# Top.net
KiCad netlist of a schematic drawn in Altium Designer
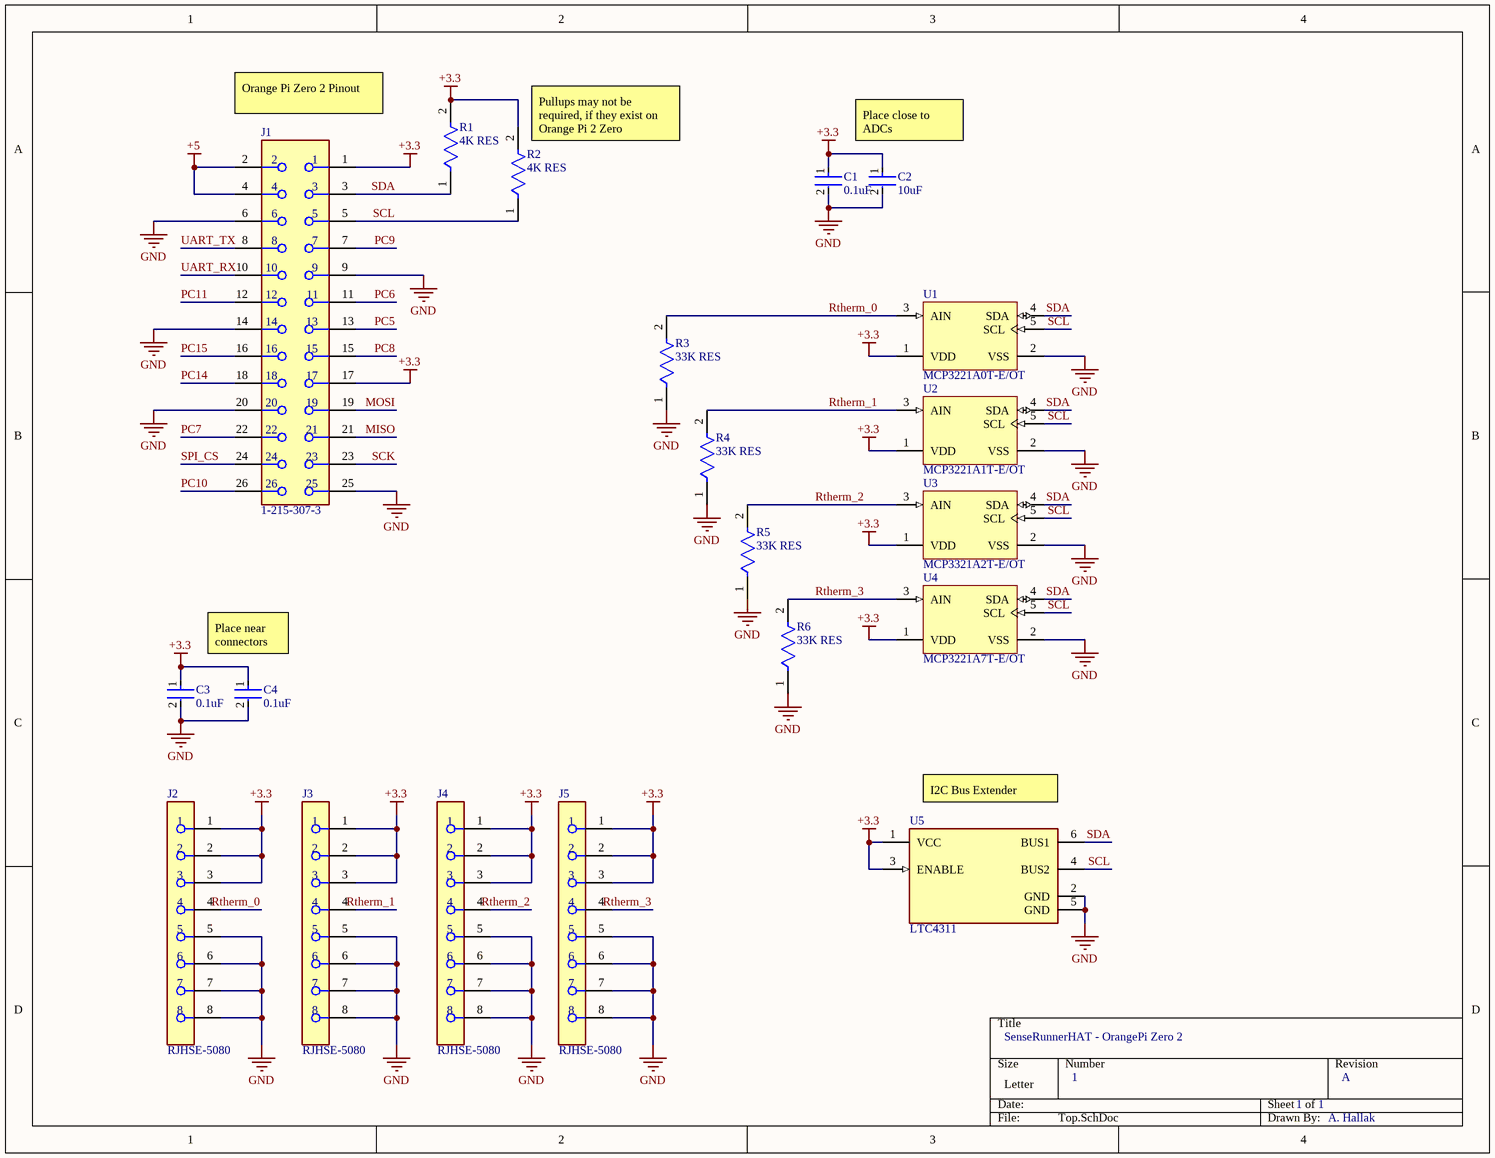
[diagram p0: Top.SchDoc]

(export (version "E")
  (design (tool "Eeschema 10.0.6"))
  (components
    (comp (ref "C1")
      (value "0.1uF")
      (footprint "FP-DE6_D7_T7_F7_5_d0_6-0-MFG")
      (description "CAP CER 0.1uF")
      (fields (field (name "PART NUMBER") "ANY 0.1uF CAP") (field (name "TOLERANCE") "20%"))
      (libsource (lib "Altium Content Vault") (part "7bc8f122f62ff4f5a687363419e79e3"))
    )
    (comp (ref "C2")
      (value "10uF")
      (footprint "FP-DE6_D7_T7_F7_5_d0_6-0-MFG")
      (description "CAP CER 10uF")
      (fields (field (name "PART NUMBER") "ANY 10uF CAP") (field (name "TOLERANCE") "20%"))
      (libsource (lib "Altium Content Vault") (part "7bc8f122f62ff4f5a687363419e79e3"))
    )
    (comp (ref "C3")
      (value "0.1uF")
      (footprint "FP-DE6_D7_T7_F7_5_d0_6-0-MFG")
      (description "CAP CER 0.1uF")
      (fields (field (name "PART NUMBER") "ANY 0.1uF CAP") (field (name "TOLERANCE") "20%"))
      (libsource (lib "Altium Content Vault") (part "7bc8f122f62ff4f5a687363419e79e3"))
    )
    (comp (ref "C4")
      (value "0.1uF")
      (footprint "FP-DE6_D7_T7_F7_5_d0_6-0-MFG")
      (description "CAP CER 0.1uF")
      (fields (field (name "PART NUMBER") "ANY 0.1uF CAP") (field (name "TOLERANCE") "20%"))
      (libsource (lib "Altium Content Vault") (part "7bc8f122f62ff4f5a687363419e79e3"))
    )
    (comp (ref "J1")
      (value "1-215-307-3")
      (footprint "Footprints:26PIN")
      (description "CONN HDR 26POS")
      (libsource (lib "Symbols") (part "CMP-25680-000025-1"))
    )
    (comp (ref "J2")
      (value "RJHSE-5080")
      (footprint "FP-RJHSE-5080-MFG")
      (description "CONN MOD JACK 8P8C R/A UNSHLD")
      (fields
        (field (name "OCTOPART") "https://octopart.com/rjhse-5080-amphenol-45060")
        (field (name "MANUFACTURER") "Amphenol")
      )
      (libsource (lib "Altium Content Vault") (part "b0a0b555dd3abf3683e7c330df25cc4"))
    )
    (comp (ref "J3")
      (value "RJHSE-5080")
      (footprint "FP-RJHSE-5080-MFG")
      (description "CONN MOD JACK 8P8C R/A UNSHLD")
      (fields
        (field (name "OCTOPART") "https://octopart.com/rjhse-5080-amphenol-45060")
        (field (name "MANUFACTURER") "Amphenol")
      )
      (libsource (lib "Altium Content Vault") (part "b0a0b555dd3abf3683e7c330df25cc4"))
    )
    (comp (ref "J4")
      (value "RJHSE-5080")
      (footprint "FP-RJHSE-5080-MFG")
      (description "CONN MOD JACK 8P8C R/A UNSHLD")
      (fields
        (field (name "OCTOPART") "https://octopart.com/rjhse-5080-amphenol-45060")
        (field (name "MANUFACTURER") "Amphenol")
      )
      (libsource (lib "Altium Content Vault") (part "b0a0b555dd3abf3683e7c330df25cc4"))
    )
    (comp (ref "J5")
      (value "RJHSE-5080")
      (footprint "FP-RJHSE-5080-MFG")
      (description "CONN MOD JACK 8P8C R/A UNSHLD")
      (fields
        (field (name "OCTOPART") "https://octopart.com/rjhse-5080-amphenol-45060")
        (field (name "MANUFACTURER") "Amphenol")
      )
      (libsource (lib "Altium Content Vault") (part "b0a0b555dd3abf3683e7c330df25cc4"))
    )
    (comp (ref "R1")
      (value "4K RES")
      (footprint "FP-H8-MFG")
      (description "RES 4K")
      (fields (field (name "PART NUMBER") "ANY 4K RESISTOR"))
      (libsource (lib "Altium Content Vault") (part "1029c3af85768c4190bb7ad29bc67b5"))
    )
    (comp (ref "R2")
      (value "4K RES")
      (footprint "FP-H8-MFG")
      (description "RES 4K")
      (fields (field (name "PART NUMBER") "ANY 4K RESISTOR"))
      (libsource (lib "Altium Content Vault") (part "1029c3af85768c4190bb7ad29bc67b5"))
    )
    (comp (ref "R3")
      (value "33K RES")
      (footprint "FP-H8-MFG")
      (description "RES 33K")
      (fields (field (name "PART NUMBER") "ANY RES - RSET"))
      (libsource (lib "Altium Content Vault") (part "1029c3af85768c4190bb7ad29bc67b5"))
    )
    (comp (ref "R4")
      (value "33K RES")
      (footprint "FP-H8-MFG")
      (description "RES 33K")
      (fields (field (name "PART NUMBER") "ANY RES - RSET"))
      (libsource (lib "Altium Content Vault") (part "1029c3af85768c4190bb7ad29bc67b5"))
    )
    (comp (ref "R5")
      (value "33K RES")
      (footprint "FP-H8-MFG")
      (description "RES 33K")
      (fields (field (name "PART NUMBER") "ANY RES - RSET"))
      (libsource (lib "Altium Content Vault") (part "1029c3af85768c4190bb7ad29bc67b5"))
    )
    (comp (ref "R6")
      (value "33K RES")
      (footprint "FP-H8-MFG")
      (description "RES 33K")
      (fields (field (name "PART NUMBER") "ANY RES - RSET"))
      (libsource (lib "Altium Content Vault") (part "1029c3af85768c4190bb7ad29bc67b5"))
    )
    (comp (ref "U1")
      (value "MCP3221A0T-E/OT")
      (footprint "SOT-23-OT5_N")
      (libsource (lib "Altium Content Vault") (part "CON-ADC-MCP3021-5"))
    )
    (comp (ref "U2")
      (value "MCP3221A1T-E/OT")
      (footprint "SOT-23-OT5_N")
      (libsource (lib "Altium Content Vault") (part "CON-ADC-MCP3021-5"))
    )
    (comp (ref "U3")
      (value "MCP3321A2T-E/OT")
      (footprint "SOT-23-OT5_N")
      (libsource (lib "Altium Content Vault") (part "CON-ADC-MCP3021-5"))
    )
    (comp (ref "U4")
      (value "MCP3221A7T-E/OT")
      (footprint "SOT-23-OT5_N")
      (fields (field (name "PART NUMBER") "MCP3321A7T-E/OT"))
      (libsource (lib "Altium Content Vault") (part "CON-ADC-MCP3021-5"))
    )
    (comp (ref "U5")
      (value "LTC4311")
      (footprint "FP-SC6-6-05-08-1638-IPC_C")
      (description "IC ACCELERATOR I2C 1CH SC70-6")
      (libsource (lib "Altium Content Vault") (part "8960268e019b227b8cf571965444921"))
    )
  )
  (nets
    (net (code "1") (name "+3.3") (class "Default")
      (node (ref "C1") (pin "1") (pinfunction "1_1") (pintype "passive"))
      (node (ref "C2") (pin "1") (pinfunction "1_1") (pintype "passive"))
      (node (ref "C3") (pin "1") (pinfunction "1_1") (pintype "passive"))
      (node (ref "C4") (pin "1") (pinfunction "1_1") (pintype "passive"))
      (node (ref "J1") (pin "1") (pinfunction "1_1") (pintype "passive"))
      (node (ref "J1") (pin "17") (pinfunction "17_17") (pintype "passive"))
      (node (ref "J2") (pin "1") (pinfunction "1_1") (pintype "passive"))
      (node (ref "J2") (pin "2") (pinfunction "2_2") (pintype "passive"))
      (node (ref "J2") (pin "3") (pinfunction "3_3") (pintype "passive"))
      (node (ref "J3") (pin "1") (pinfunction "1_1") (pintype "passive"))
      (node (ref "J3") (pin "2") (pinfunction "2_2") (pintype "passive"))
      (node (ref "J3") (pin "3") (pinfunction "3_3") (pintype "passive"))
      (node (ref "J4") (pin "1") (pinfunction "1_1") (pintype "passive"))
      (node (ref "J4") (pin "2") (pinfunction "2_2") (pintype "passive"))
      (node (ref "J4") (pin "3") (pinfunction "3_3") (pintype "passive"))
      (node (ref "J5") (pin "1") (pinfunction "1_1") (pintype "passive"))
      (node (ref "J5") (pin "2") (pinfunction "2_2") (pintype "passive"))
      (node (ref "J5") (pin "3") (pinfunction "3_3") (pintype "passive"))
      (node (ref "R1") (pin "2") (pinfunction "2_2") (pintype "passive"))
      (node (ref "R2") (pin "2") (pinfunction "2_2") (pintype "passive"))
      (node (ref "U1") (pin "1") (pinfunction "VDD_1") (pintype "power_in"))
      (node (ref "U2") (pin "1") (pinfunction "VDD_1") (pintype "power_in"))
      (node (ref "U3") (pin "1") (pinfunction "VDD_1") (pintype "power_in"))
      (node (ref "U4") (pin "1") (pinfunction "VDD_1") (pintype "power_in"))
      (node (ref "U5") (pin "1") (pinfunction "VCC_1") (pintype "power_in"))
      (node (ref "U5") (pin "3") (pinfunction "ENABLE_3") (pintype "input"))
    )
    (net (code "2") (name "+5") (class "Default")
      (node (ref "J1") (pin "2") (pinfunction "2_2") (pintype "passive"))
      (node (ref "J1") (pin "4") (pinfunction "4_4") (pintype "passive"))
    )
    (net (code "3") (name "/MISO") (class "Default")
      (node (ref "J1") (pin "21") (pinfunction "21_21") (pintype "passive"))
    )
    (net (code "4") (name "/MOSI") (class "Default")
      (node (ref "J1") (pin "19") (pinfunction "19_19") (pintype "passive"))
    )
    (net (code "5") (name "/PC5") (class "Default")
      (node (ref "J1") (pin "13") (pinfunction "13_13") (pintype "passive"))
    )
    (net (code "6") (name "/PC6") (class "Default")
      (node (ref "J1") (pin "11") (pinfunction "11_11") (pintype "passive"))
    )
    (net (code "7") (name "/PC7") (class "Default")
      (node (ref "J1") (pin "22") (pinfunction "22_22") (pintype "passive"))
    )
    (net (code "8") (name "/PC8") (class "Default")
      (node (ref "J1") (pin "15") (pinfunction "15_15") (pintype "passive"))
    )
    (net (code "9") (name "/PC9") (class "Default")
      (node (ref "J1") (pin "7") (pinfunction "7_7") (pintype "passive"))
    )
    (net (code "10") (name "/PC10") (class "Default")
      (node (ref "J1") (pin "26") (pinfunction "26_26") (pintype "passive"))
    )
    (net (code "11") (name "/PC11") (class "Default")
      (node (ref "J1") (pin "12") (pinfunction "12_12") (pintype "passive"))
    )
    (net (code "12") (name "/PC14") (class "Default")
      (node (ref "J1") (pin "18") (pinfunction "18_18") (pintype "passive"))
    )
    (net (code "13") (name "/PC15") (class "Default")
      (node (ref "J1") (pin "16") (pinfunction "16_16") (pintype "passive"))
    )
    (net (code "14") (name "/Rtherm_0") (class "Default")
      (node (ref "J2") (pin "4") (pinfunction "4_4") (pintype "passive"))
      (node (ref "R3") (pin "2") (pinfunction "2_2") (pintype "passive"))
      (node (ref "U1") (pin "3") (pinfunction "AIN_3") (pintype "input"))
    )
    (net (code "15") (name "/Rtherm_1") (class "Default")
      (node (ref "J3") (pin "4") (pinfunction "4_4") (pintype "passive"))
      (node (ref "R4") (pin "2") (pinfunction "2_2") (pintype "passive"))
      (node (ref "U2") (pin "3") (pinfunction "AIN_3") (pintype "input"))
    )
    (net (code "16") (name "/Rtherm_2") (class "Default")
      (node (ref "J4") (pin "4") (pinfunction "4_4") (pintype "passive"))
      (node (ref "R5") (pin "2") (pinfunction "2_2") (pintype "passive"))
      (node (ref "U3") (pin "3") (pinfunction "AIN_3") (pintype "input"))
    )
    (net (code "17") (name "/Rtherm_3") (class "Default")
      (node (ref "J5") (pin "4") (pinfunction "4_4") (pintype "passive"))
      (node (ref "R6") (pin "2") (pinfunction "2_2") (pintype "passive"))
      (node (ref "U4") (pin "3") (pinfunction "AIN_3") (pintype "input"))
    )
    (net (code "18") (name "/SCK") (class "Default")
      (node (ref "J1") (pin "23") (pinfunction "23_23") (pintype "passive"))
    )
    (net (code "19") (name "/SCL") (class "Default")
      (node (ref "J1") (pin "5") (pinfunction "5_5") (pintype "passive"))
      (node (ref "R2") (pin "1") (pinfunction "1_1") (pintype "passive"))
      (node (ref "U1") (pin "5") (pinfunction "SCL_5") (pintype "input"))
      (node (ref "U2") (pin "5") (pinfunction "SCL_5") (pintype "input"))
      (node (ref "U3") (pin "5") (pinfunction "SCL_5") (pintype "input"))
      (node (ref "U4") (pin "5") (pinfunction "SCL_5") (pintype "input"))
      (node (ref "U5") (pin "4") (pinfunction "BUS2_4") (pintype "passive"))
    )
    (net (code "20") (name "/SDA") (class "Default")
      (node (ref "J1") (pin "3") (pinfunction "3_3") (pintype "passive"))
      (node (ref "R1") (pin "1") (pinfunction "1_1") (pintype "passive"))
      (node (ref "U1") (pin "4") (pinfunction "SDA_4") (pintype "bidirectional"))
      (node (ref "U2") (pin "4") (pinfunction "SDA_4") (pintype "bidirectional"))
      (node (ref "U3") (pin "4") (pinfunction "SDA_4") (pintype "bidirectional"))
      (node (ref "U4") (pin "4") (pinfunction "SDA_4") (pintype "bidirectional"))
      (node (ref "U5") (pin "6") (pinfunction "BUS1_6") (pintype "passive"))
    )
    (net (code "21") (name "/SPI_CS") (class "Default")
      (node (ref "J1") (pin "24") (pinfunction "24_24") (pintype "passive"))
    )
    (net (code "22") (name "/UART_RX") (class "Default")
      (node (ref "J1") (pin "10") (pinfunction "10_10") (pintype "passive"))
    )
    (net (code "23") (name "/UART_TX") (class "Default")
      (node (ref "J1") (pin "8") (pinfunction "8_8") (pintype "passive"))
    )
    (net (code "24") (name "GND") (class "Default")
      (node (ref "C1") (pin "2") (pinfunction "2_2") (pintype "passive"))
      (node (ref "C2") (pin "2") (pinfunction "2_2") (pintype "passive"))
      (node (ref "C3") (pin "2") (pinfunction "2_2") (pintype "passive"))
      (node (ref "C4") (pin "2") (pinfunction "2_2") (pintype "passive"))
      (node (ref "J1") (pin "14") (pinfunction "14_14") (pintype "passive"))
      (node (ref "J1") (pin "20") (pinfunction "20_20") (pintype "passive"))
      (node (ref "J1") (pin "25") (pinfunction "25_25") (pintype "passive"))
      (node (ref "J1") (pin "6") (pinfunction "6_6") (pintype "passive"))
      (node (ref "J1") (pin "9") (pinfunction "9_9") (pintype "passive"))
      (node (ref "J2") (pin "5") (pinfunction "5_5") (pintype "passive"))
      (node (ref "J2") (pin "6") (pinfunction "6_6") (pintype "passive"))
      (node (ref "J2") (pin "7") (pinfunction "7_7") (pintype "passive"))
      (node (ref "J2") (pin "8") (pinfunction "8_8") (pintype "passive"))
      (node (ref "J3") (pin "5") (pinfunction "5_5") (pintype "passive"))
      (node (ref "J3") (pin "6") (pinfunction "6_6") (pintype "passive"))
      (node (ref "J3") (pin "7") (pinfunction "7_7") (pintype "passive"))
      (node (ref "J3") (pin "8") (pinfunction "8_8") (pintype "passive"))
      (node (ref "J4") (pin "5") (pinfunction "5_5") (pintype "passive"))
      (node (ref "J4") (pin "6") (pinfunction "6_6") (pintype "passive"))
      (node (ref "J4") (pin "7") (pinfunction "7_7") (pintype "passive"))
      (node (ref "J4") (pin "8") (pinfunction "8_8") (pintype "passive"))
      (node (ref "J5") (pin "5") (pinfunction "5_5") (pintype "passive"))
      (node (ref "J5") (pin "6") (pinfunction "6_6") (pintype "passive"))
      (node (ref "J5") (pin "7") (pinfunction "7_7") (pintype "passive"))
      (node (ref "J5") (pin "8") (pinfunction "8_8") (pintype "passive"))
      (node (ref "R3") (pin "1") (pinfunction "1_1") (pintype "passive"))
      (node (ref "R4") (pin "1") (pinfunction "1_1") (pintype "passive"))
      (node (ref "R5") (pin "1") (pinfunction "1_1") (pintype "passive"))
      (node (ref "R6") (pin "1") (pinfunction "1_1") (pintype "passive"))
      (node (ref "U1") (pin "2") (pinfunction "VSS_2") (pintype "power_in"))
      (node (ref "U2") (pin "2") (pinfunction "VSS_2") (pintype "power_in"))
      (node (ref "U3") (pin "2") (pinfunction "VSS_2") (pintype "power_in"))
      (node (ref "U4") (pin "2") (pinfunction "VSS_2") (pintype "power_in"))
      (node (ref "U5") (pin "2") (pinfunction "GND_2") (pintype "power_in"))
      (node (ref "U5") (pin "5") (pinfunction "GND_5") (pintype "power_in"))
    )
  )
)
